# Schema2.net
KiCad netlist of a schematic drawn in Altium Designer
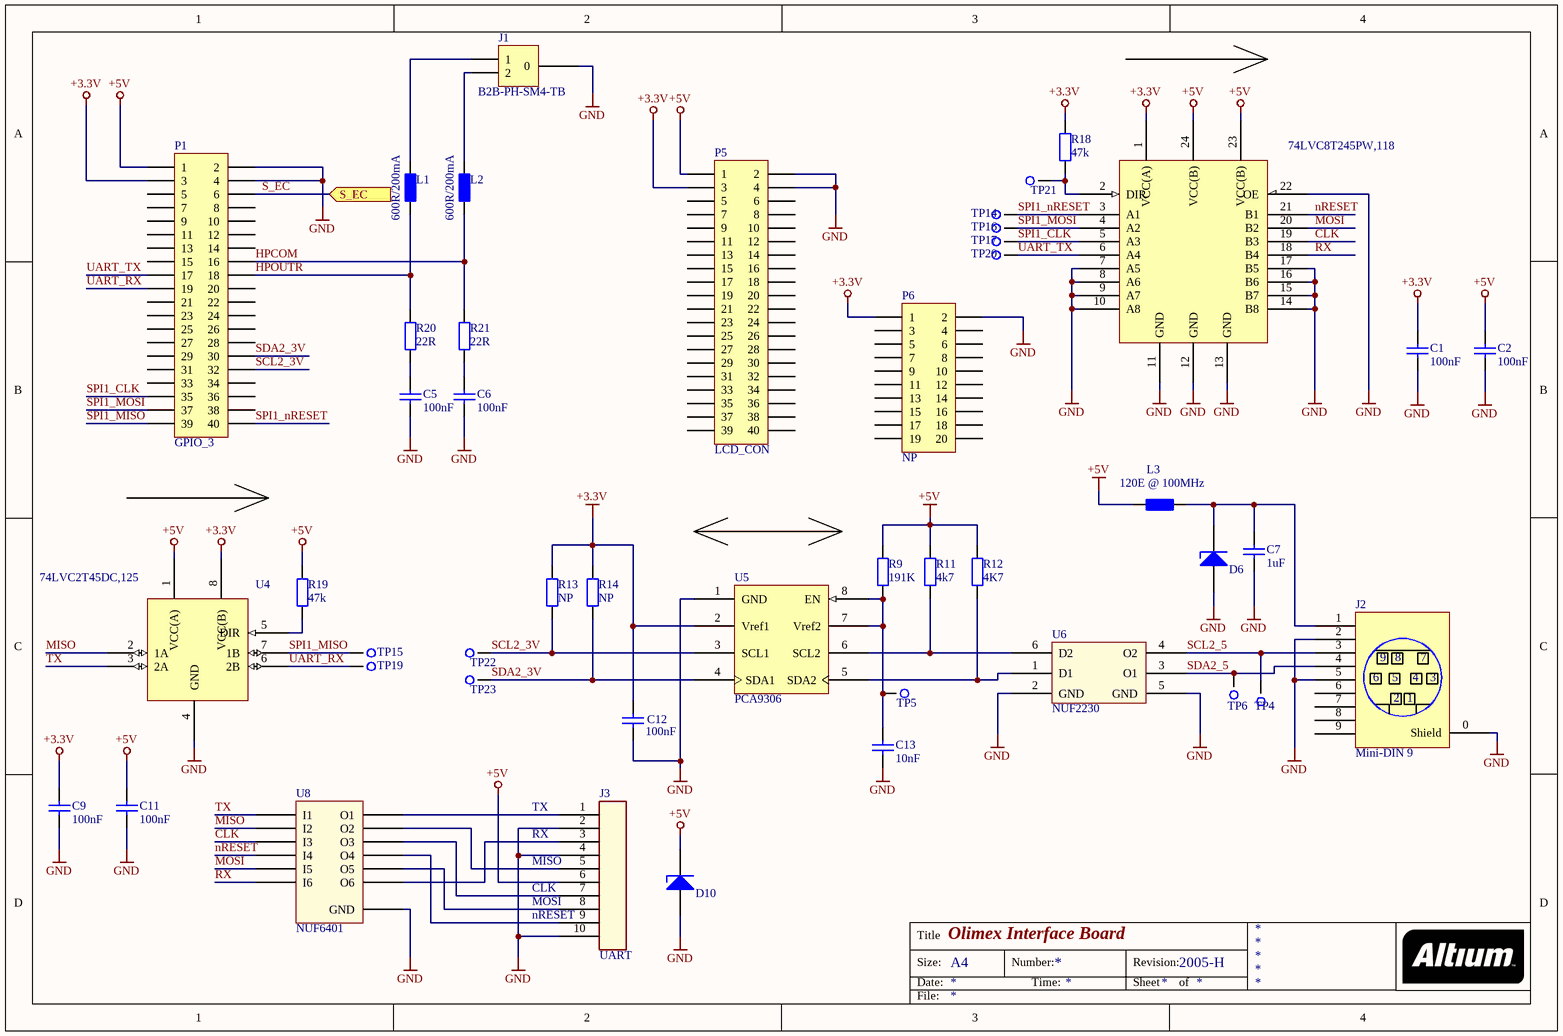
[diagram p0: Schema2.SchDoc]

(export (version "E")
  (design (tool "Eeschema 10.0.6"))
  (components
    (comp (ref "C1")
      (value "100nF")
      (footprint "C0805 (2012)")
      (description "Cap 100nF X7R 0805 10% 100V")
      (fields (field (name "MFG") "AVX"))
      (libsource (lib "Faber_SCH_lib") (part "Cap 100nF X7R 0805"))
    )
    (comp (ref "C2")
      (value "100nF")
      (footprint "C0805 (2012)")
      (description "Cap 100nF X7R 0805 10% 100V")
      (fields (field (name "MFG") "AVX"))
      (libsource (lib "Faber_SCH_lib") (part "Cap 100nF X7R 0805"))
    )
    (comp (ref "C5")
      (value "100nF")
      (footprint "C0805 (2012)")
      (description "Cap 100nF X7R 0805 10% 100V")
      (fields (field (name "MFG") "AVX"))
      (libsource (lib "Faber_SCH_lib") (part "Cap 100nF X7R 0805"))
    )
    (comp (ref "C6")
      (value "100nF")
      (footprint "C0805 (2012)")
      (description "Cap 100nF X7R 0805 10% 100V")
      (fields (field (name "MFG") "AVX"))
      (libsource (lib "Faber_SCH_lib") (part "Cap 100nF X7R 0805"))
    )
    (comp (ref "C7")
      (value "1uF")
      (footprint "CAPC1608X09N")
      (description "CAP CER 1UF 10V 10% X5R 0603")
      (fields
        (field (name "MANUFACTURER") "Murata Electronics North America")
        (field (name "MANUFACTURER PART NUMBER") "GRM188R61A105KA61D")
      )
      (libsource (lib "Marlin") (part "1uF/10V/0603"))
    )
    (comp (ref "C9")
      (value "100nF")
      (footprint "C0805 (2012)")
      (description "Cap 100nF X7R 0805 10% 100V")
      (fields (field (name "MFG") "AVX"))
      (libsource (lib "Faber_SCH_lib") (part "Cap 100nF X7R 0805"))
    )
    (comp (ref "C11")
      (value "100nF")
      (footprint "C0805 (2012)")
      (description "Cap 100nF X7R 0805 10% 100V")
      (fields (field (name "MFG") "AVX"))
      (libsource (lib "Faber_SCH_lib") (part "Cap 100nF X7R 0805"))
    )
    (comp (ref "C12")
      (value "100nF")
      (footprint "C0805 (2012)")
      (description "Cap 100nF X7R 0805 10% 100V")
      (fields (field (name "MFG") "AVX"))
      (libsource (lib "Faber_SCH_lib") (part "Cap 100nF X7R 0805"))
    )
    (comp (ref "C13")
      (value "10nF")
      (footprint "C0805 (2012)")
      (description "Cap 10nF X7R 0805 10% 100V")
      (fields (field (name "MFG") "AVX"))
      (libsource (lib "Faber_SCH_lib") (part "Cap 10nF X7R 0805"))
    )
    (comp (ref "D6")
      (value "ESD9X5.0ST5G")
      (footprint "SODFL100X40-2N")
      (description "TVS DIODE 5VWM 12.3VC SOD923")
      (fields (field (name "MFG") "ON Semiconductor"))
      (libsource (lib "Olimex interface board") (part "ESD9X5.0ST5G"))
    )
    (comp (ref "D10")
      (value "ESD9X5.0ST5G")
      (footprint "SODFL100X40-2N")
      (description "TVS DIODE 5VWM 12.3VC SOD923")
      (fields (field (name "MFG") "ON Semiconductor"))
      (libsource (lib "Olimex interface board") (part "ESD9X5.0ST5G"))
    )
    (comp (ref "J1")
      (value "B2B-PH-SM4-TB")
      (footprint "B2B-PH-SM4-TB")
      (description "JST B2B-PH-SM4-TB")
      (fields (field (name "MFG") "JST"))
      (libsource (lib "Olimex interface board") (part "Header 2_1"))
    )
    (comp (ref "J2")
      (value "Mini-DIN 9")
      (footprint "MD-90SM")
      (fields (field (name "MFG") "CUI Inc."))
      (libsource (lib "Olimex interface board") (part "Mini-DIN 9"))
    )
    (comp (ref "J3")
      (value "UART")
      (footprint "BOXHEADER-10P-straight")
      (description "RO CONN PR HDR BOX 10p")
      (fields (field (name "MFG") "Wurth"))
      (libsource (lib "Database_Faber") (part "HEADER 10"))
    )
    (comp (ref "L1")
      (value "600R/200mA")
      (footprint "R0805")
      (fields (field (name "MFG") "Fair-rite"))
      (libsource (lib "Ultimaker") (part "Ferriet Bead 600E"))
    )
    (comp (ref "L2")
      (value "600R/200mA")
      (footprint "R0805")
      (fields (field (name "MFG") "Fair-rite"))
      (libsource (lib "Ultimaker") (part "Ferriet Bead 600E"))
    )
    (comp (ref "L3")
      (value "120E @ 100MHz")
      (footprint "R0603")
      (description "FERRIET BLM18PG121SN1D 0603 MURATA")
      (fields (field (name "MFG") "Murata"))
      (libsource (lib "Ultimaker") (part "Ferriet Bead 120E"))
    )
    (comp (ref "P1")
      (value "GPIO_3")
      (footprint "M50-3152042")
      (description "HARWIN - M50-3152042 - SOCKET, DUAL ENTRY, SMT, 40WAY")
      (fields (field (name "MFG") "Harwin") (field (name "PUBLISHER") "Altium Limited"))
      (libsource (lib "Olimex interface board_1") (part "MHDR2X20"))
    )
    (comp (ref "P5")
      (value "LCD_CON")
      (footprint "M50-3152042")
      (description "HARWIN - M50-3152042 - SOCKET, DUAL ENTRY, SMT, 40WAY")
      (fields (field (name "MFG") "Harwin") (field (name "PUBLISHER") "Altium Limited"))
      (libsource (lib "Olimex interface board_1") (part "MHDR2X20"))
    )
    (comp (ref "P6")
      (value "NP")
      (footprint "HARWIN M20")
      (description "HARWIN M20")
      (fields (field (name "PUBLISHER") "Altium Limited"))
      (libsource (lib "Miscellaneous Connectors") (part "MHDR2X10"))
    )
    (comp (ref "R9")
      (value "191K")
      (footprint "R0805 (2012)")
      (description "Res 191K 0805 1% 125mW")
      (fields (field (name "MFG") "VISHAY DRALORIC"))
      (libsource (lib "Faber_SCH_lib") (part "Res 191K 0805"))
    )
    (comp (ref "R11")
      (value "4k7")
      (footprint "RESC1608X05N")
      (description "RES SMD 4.7K OHM 1% 1/10W 0603")
      (fields
        (field (name "MANUFACTURER") "Vishay Dale")
        (field (name "MANUFACTURER PART NUMBER") "CRCW06034K70FKEA")
      )
      (libsource (lib "altium-import") (part "root_1__Faber_SCH_lib.SchLib"))
    )
    (comp (ref "R12")
      (value "4K7")
      (footprint "RESC1608X05N")
      (description "RES SMD 4.7K OHM 1% 1/10W 0603")
      (fields
        (field (name "MANUFACTURER") "Vishay Dale")
        (field (name "MANUFACTURER PART NUMBER") "CRCW06034K70FKEA")
      )
      (libsource (lib "altium-import") (part "root_1__Faber_SCH_lib.SchLib"))
    )
    (comp (ref "R13")
      (value "NP")
      (footprint "R0805 (2012)")
      (description "Res 4.7K 0805 1% 100mW")
      (fields (field (name "MFG") "MULTICOMP"))
      (libsource (lib "Faber_SCH_lib") (part "Res 4.7K 0805"))
    )
    (comp (ref "R14")
      (value "NP")
      (footprint "R0805 (2012)")
      (description "Res 4.7K 0805 1% 100mW")
      (fields (field (name "MFG") "MULTICOMP"))
      (libsource (lib "Faber_SCH_lib") (part "Res 4.7K 0805"))
    )
    (comp (ref "R18")
      (value "47k")
      (footprint "RESC1608X05N")
      (description "RES 47.0K OHM 1/10W 1% 0603 SMD")
      (fields
        (field (name "MANUFACTURER") "Vishay Dale")
        (field (name "MANUFACTURER PART NUMBER") "CRCW060347K0FKEA")
      )
      (libsource (lib "Marlin") (part "47k/0603"))
    )
    (comp (ref "R19")
      (value "47k")
      (footprint "RESC1608X05N")
      (description "RES 47.0K OHM 1/10W 1% 0603 SMD")
      (fields
        (field (name "MANUFACTURER") "Vishay Dale")
        (field (name "MANUFACTURER PART NUMBER") "CRCW060347K0FKEA")
      )
      (libsource (lib "Marlin") (part "47k/0603"))
    )
    (comp (ref "R20")
      (value "22R")
      (footprint "RESC1608X05N")
      (description "RES 22R OHM 63mW 1% 0603 SMD")
      (fields (field (name "MFG") "MULTICOMP"))
      (libsource (lib "altium-import") (part "root_1_2.2k/0603_"))
    )
    (comp (ref "R21")
      (value "22R")
      (footprint "RESC1608X05N")
      (description "RES 22R OHM 63mW 1% 0603 SMD")
      (fields (field (name "MFG") "MULTICOMP"))
      (libsource (lib "altium-import") (part "root_1_2.2k/0603_"))
    )
    (comp (ref "TP4")
      (value "2mm")
      (footprint "TESTPOINT 2mm")
      (description "Testpoint, 2mm, round")
      (libsource (lib "Faber_SCH_lib") (part "Testpoint, 2mm, round"))
    )
    (comp (ref "TP5")
      (value "2mm")
      (footprint "TESTPOINT 2mm")
      (description "Testpoint, 2mm, round")
      (libsource (lib "Faber_SCH_lib") (part "Testpoint, 2mm, round"))
    )
    (comp (ref "TP6")
      (value "2mm")
      (footprint "TESTPOINT 2mm")
      (description "Testpoint, 2mm, round")
      (libsource (lib "Faber_SCH_lib") (part "Testpoint, 2mm, round"))
    )
    (comp (ref "TP14")
      (value "2mm")
      (footprint "TESTPOINT 2mm")
      (description "Testpoint, 2mm, round")
      (libsource (lib "Faber_SCH_lib") (part "Testpoint, 2mm, round"))
    )
    (comp (ref "TP15")
      (value "2mm")
      (footprint "TESTPOINT 2mm")
      (description "Testpoint, 2mm, round")
      (libsource (lib "Faber_SCH_lib") (part "Testpoint, 2mm, round"))
    )
    (comp (ref "TP16")
      (value "2mm")
      (footprint "TESTPOINT 2mm")
      (description "Testpoint, 2mm, round")
      (libsource (lib "Faber_SCH_lib") (part "Testpoint, 2mm, round"))
    )
    (comp (ref "TP17")
      (value "2mm")
      (footprint "TESTPOINT 2mm")
      (description "Testpoint, 2mm, round")
      (libsource (lib "Faber_SCH_lib") (part "Testpoint, 2mm, round"))
    )
    (comp (ref "TP19")
      (value "2mm")
      (footprint "TESTPOINT 2mm")
      (description "Testpoint, 2mm, round")
      (libsource (lib "Faber_SCH_lib") (part "Testpoint, 2mm, round"))
    )
    (comp (ref "TP20")
      (value "2mm")
      (footprint "TESTPOINT 2mm")
      (description "Testpoint, 2mm, round")
      (libsource (lib "Faber_SCH_lib") (part "Testpoint, 2mm, round"))
    )
    (comp (ref "TP21")
      (value "2mm")
      (footprint "TESTPOINT 2mm")
      (description "Testpoint, 2mm, round")
      (libsource (lib "Faber_SCH_lib") (part "Testpoint, 2mm, round"))
    )
    (comp (ref "TP22")
      (value "2mm")
      (footprint "TESTPOINT 2mm")
      (description "Testpoint, 2mm, round")
      (libsource (lib "Faber_SCH_lib") (part "Testpoint, 2mm, round"))
    )
    (comp (ref "TP23")
      (value "2mm")
      (footprint "TESTPOINT 2mm")
      (description "Testpoint, 2mm, round")
      (libsource (lib "Faber_SCH_lib") (part "Testpoint, 2mm, round"))
    )
    (comp (ref "U3")
      (value "74LVC8T245PW,118")
      (footprint "TSOP65P640X110-24N")
      (description "8-bit translaing transceiver")
      (fields (field (name "MFG") "NXP"))
      (libsource (lib "Olimex interface board") (part "74LVC8T245PW,118"))
    )
    (comp (ref "U4")
      (value "74LVC2T45DC,125")
      (footprint "TSSOP50P310X100-8N")
      (description "2-bit translaing transceiver")
      (fields (field (name "MFG") "NXP"))
      (libsource (lib "Olimex interface board") (part "74LVC2T45DC,125"))
    )
    (comp (ref "U5")
      (value "PCA9306")
      (footprint "IC SSOP-8")
      (description "IC PCA9306 Voltage Level translator")
      (fields (field (name "MFG") "TEXAS INSTRUMENTS"))
      (libsource (lib "Faber_SCH_lib") (part "IC PCA9306"))
    )
    (comp (ref "U6")
      (value "NUF2230")
      (footprint "SOTFL50P160X60-6N")
      (fields (field (name "MFG") "ON Semiconductor"))
      (libsource (lib "printehead") (part "NUF2230"))
    )
    (comp (ref "U8")
      (value "NUF6401")
      (footprint "SON50P140X100_HS-13N")
      (fields (field (name "MFG") "ON Semiconductor"))
      (libsource (lib "UltiController") (part "NUF6401"))
    )
  )
  (nets
    (net (code "1") (name "+3.3V") (class "Default")
      (node (ref "C1") (pin "1") (pinfunction "1_1") (pintype "passive"))
      (node (ref "C12") (pin "2") (pinfunction "2_2") (pintype "passive"))
      (node (ref "C9") (pin "1") (pinfunction "1_1") (pintype "passive"))
      (node (ref "P1") (pin "3") (pinfunction "3_3") (pintype "passive"))
      (node (ref "P5") (pin "3") (pinfunction "3_3") (pintype "passive"))
      (node (ref "P6") (pin "1") (pinfunction "1_1") (pintype "passive"))
      (node (ref "R13") (pin "2") (pinfunction "2_2") (pintype "passive"))
      (node (ref "R14") (pin "2") (pinfunction "2_2") (pintype "passive"))
      (node (ref "R18") (pin "1") (pinfunction "1_1") (pintype "passive"))
      (node (ref "U3") (pin "1") (pinfunction "VCC(A)_1") (pintype "power_in"))
      (node (ref "U4") (pin "8") (pinfunction "VCC(B)_8") (pintype "power_in"))
      (node (ref "U5") (pin "2") (pinfunction "Vref1_2") (pintype "power_in"))
    )
    (net (code "2") (name "+5V") (class "Default")
      (node (ref "C11") (pin "1") (pinfunction "1_1") (pintype "passive"))
      (node (ref "C2") (pin "1") (pinfunction "1_1") (pintype "passive"))
      (node (ref "D10") (pin "1") (pinfunction "K_1") (pintype "passive"))
      (node (ref "J3") (pin "6") (pinfunction "6_6") (pintype "passive"))
      (node (ref "L3") (pin "1") (pinfunction "1_1") (pintype "passive"))
      (node (ref "P1") (pin "1") (pinfunction "1_1") (pintype "passive"))
      (node (ref "P5") (pin "1") (pinfunction "1_1") (pintype "passive"))
      (node (ref "R11") (pin "2") (pinfunction "2_2") (pintype "passive"))
      (node (ref "R12") (pin "2") (pinfunction "2_2") (pintype "passive"))
      (node (ref "R19") (pin "1") (pinfunction "1_1") (pintype "passive"))
      (node (ref "R9") (pin "2") (pinfunction "2_2") (pintype "passive"))
      (node (ref "U3") (pin "23") (pinfunction "VCC(B)_23") (pintype "power_in"))
      (node (ref "U3") (pin "24") (pinfunction "VCC(B)_24") (pintype "power_in"))
      (node (ref "U4") (pin "1") (pinfunction "VCC(A)_1") (pintype "power_in"))
    )
    (net (code "3") (name "/CLK") (class "Default")
      (node (ref "U3") (pin "19") (pinfunction "B3_19") (pintype "passive"))
      (node (ref "U8") (pin "3") (pinfunction "I3_3") (pintype "passive"))
    )
    (net (code "4") (name "/HPCOM") (class "Default")
      (node (ref "L2") (pin "1") (pinfunction "1_1") (pintype "passive"))
      (node (ref "P1") (pin "16") (pinfunction "16_16") (pintype "passive"))
      (node (ref "R21") (pin "2") (pinfunction "2_2") (pintype "passive"))
    )
    (net (code "5") (name "/HPOUTR") (class "Default")
      (node (ref "L1") (pin "1") (pinfunction "1_1") (pintype "passive"))
      (node (ref "P1") (pin "18") (pinfunction "18_18") (pintype "passive"))
      (node (ref "R20") (pin "2") (pinfunction "2_2") (pintype "passive"))
    )
    (net (code "6") (name "/MISO") (class "Default")
      (node (ref "U4") (pin "2") (pinfunction "1A_2") (pintype "bidirectional"))
      (node (ref "U8") (pin "2") (pinfunction "I2_2") (pintype "passive"))
    )
    (net (code "7") (name "/MOSI") (class "Default")
      (node (ref "U3") (pin "20") (pinfunction "B2_20") (pintype "passive"))
      (node (ref "U8") (pin "5") (pinfunction "I5_5") (pintype "passive"))
    )
    (net (code "8") (name "/RX") (class "Default")
      (node (ref "U3") (pin "18") (pinfunction "B4_18") (pintype "passive"))
      (node (ref "U8") (pin "6") (pinfunction "I6_6") (pintype "passive"))
    )
    (net (code "9") (name "/SCL2_3V") (class "Default")
      (node (ref "P1") (pin "32") (pinfunction "32_32") (pintype "passive"))
      (node (ref "R13") (pin "1") (pinfunction "1_1") (pintype "passive"))
      (node (ref "TP22") (pin "1") (pinfunction "1_1") (pintype "passive"))
      (node (ref "U5") (pin "3") (pinfunction "SCL1_3") (pintype "passive"))
    )
    (net (code "10") (name "/SCL2_5") (class "Default")
      (node (ref "J2") (pin "3") (pinfunction "3_3") (pintype "passive"))
      (node (ref "TP4") (pin "1") (pinfunction "1_1") (pintype "passive"))
      (node (ref "U6") (pin "4") (pinfunction "O2_4") (pintype "passive"))
    )
    (net (code "11") (name "/SDA2_3V") (class "Default")
      (node (ref "P1") (pin "30") (pinfunction "30_30") (pintype "passive"))
      (node (ref "R14") (pin "1") (pinfunction "1_1") (pintype "passive"))
      (node (ref "TP23") (pin "1") (pinfunction "1_1") (pintype "passive"))
      (node (ref "U5") (pin "4") (pinfunction "SDA1_4") (pintype "passive"))
    )
    (net (code "12") (name "/SDA2_5") (class "Default")
      (node (ref "J2") (pin "4") (pinfunction "4_4") (pintype "passive"))
      (node (ref "TP6") (pin "1") (pinfunction "1_1") (pintype "passive"))
      (node (ref "U6") (pin "3") (pinfunction "O1_3") (pintype "passive"))
    )
    (net (code "13") (name "/SPI1_CLK") (class "Default")
      (node (ref "P1") (pin "35") (pinfunction "35_35") (pintype "passive"))
      (node (ref "TP17") (pin "1") (pinfunction "1_1") (pintype "passive"))
      (node (ref "U3") (pin "5") (pinfunction "A3_5") (pintype "passive"))
    )
    (net (code "14") (name "/SPI1_MISO") (class "Default")
      (node (ref "P1") (pin "39") (pinfunction "39_39") (pintype "passive"))
      (node (ref "TP15") (pin "1") (pinfunction "1_1") (pintype "passive"))
      (node (ref "U4") (pin "7") (pinfunction "1B_7") (pintype "bidirectional"))
    )
    (net (code "15") (name "/SPI1_MOSI") (class "Default")
      (node (ref "P1") (pin "37") (pinfunction "37_37") (pintype "passive"))
      (node (ref "TP16") (pin "1") (pinfunction "1_1") (pintype "passive"))
      (node (ref "U3") (pin "4") (pinfunction "A2_4") (pintype "passive"))
    )
    (net (code "16") (name "/SPI1_nRESET") (class "Default")
      (node (ref "P1") (pin "40") (pinfunction "40_40") (pintype "passive"))
      (node (ref "TP14") (pin "1") (pinfunction "1_1") (pintype "passive"))
      (node (ref "U3") (pin "3") (pinfunction "A1_3") (pintype "passive"))
    )
    (net (code "17") (name "/S_EC") (class "Default")
      (node (ref "P1") (pin "6") (pinfunction "6_6") (pintype "passive"))
    )
    (net (code "18") (name "/TX") (class "Default")
      (node (ref "U4") (pin "3") (pinfunction "2A_3") (pintype "bidirectional"))
      (node (ref "U8") (pin "1") (pinfunction "I1_1") (pintype "passive"))
    )
    (net (code "19") (name "/UART_RX") (class "Default")
      (node (ref "P1") (pin "19") (pinfunction "19_19") (pintype "passive"))
      (node (ref "TP19") (pin "1") (pinfunction "1_1") (pintype "passive"))
      (node (ref "U4") (pin "6") (pinfunction "2B_6") (pintype "bidirectional"))
    )
    (net (code "20") (name "/UART_TX") (class "Default")
      (node (ref "P1") (pin "17") (pinfunction "17_17") (pintype "passive"))
      (node (ref "TP20") (pin "1") (pinfunction "1_1") (pintype "passive"))
      (node (ref "U3") (pin "6") (pinfunction "A4_6") (pintype "passive"))
    )
    (net (code "21") (name "/nRESET") (class "Default")
      (node (ref "U3") (pin "21") (pinfunction "B1_21") (pintype "passive"))
      (node (ref "U8") (pin "4") (pinfunction "I4_4") (pintype "passive"))
    )
    (net (code "22") (name "GND") (class "Default")
      (node (ref "C1") (pin "2") (pinfunction "2_2") (pintype "passive"))
      (node (ref "C11") (pin "2") (pinfunction "2_2") (pintype "passive"))
      (node (ref "C12") (pin "1") (pinfunction "1_1") (pintype "passive"))
      (node (ref "C13") (pin "1") (pinfunction "1_1") (pintype "passive"))
      (node (ref "C2") (pin "2") (pinfunction "2_2") (pintype "passive"))
      (node (ref "C5") (pin "2") (pinfunction "2_2") (pintype "passive"))
      (node (ref "C6") (pin "2") (pinfunction "2_2") (pintype "passive"))
      (node (ref "C7") (pin "1") (pinfunction "1_1") (pintype "passive"))
      (node (ref "C9") (pin "2") (pinfunction "2_2") (pintype "passive"))
      (node (ref "D10") (pin "2") (pinfunction "A_2") (pintype "passive"))
      (node (ref "D6") (pin "2") (pinfunction "A_2") (pintype "passive"))
      (node (ref "J1") (pin "0") (pinfunction "0_0") (pintype "passive"))
      (node (ref "J2") (pin "0") (pinfunction "Shield_0") (pintype "passive"))
      (node (ref "J2") (pin "2") (pinfunction "2_2") (pintype "passive"))
      (node (ref "J2") (pin "5") (pinfunction "5_5") (pintype "passive"))
      (node (ref "J3") (pin "10") (pinfunction "10_10") (pintype "passive"))
      (node (ref "J3") (pin "2") (pinfunction "2_2") (pintype "passive"))
      (node (ref "J3") (pin "4") (pinfunction "4_4") (pintype "passive"))
      (node (ref "P1") (pin "2") (pinfunction "2_2") (pintype "passive"))
      (node (ref "P1") (pin "4") (pinfunction "4_4") (pintype "passive"))
      (node (ref "P5") (pin "2") (pinfunction "2_2") (pintype "passive"))
      (node (ref "P5") (pin "4") (pinfunction "4_4") (pintype "passive"))
      (node (ref "P6") (pin "2") (pinfunction "2_2") (pintype "passive"))
      (node (ref "U3") (pin "10") (pinfunction "A8_10") (pintype "passive"))
      (node (ref "U3") (pin "11") (pinfunction "GND_11") (pintype "power_in"))
      (node (ref "U3") (pin "12") (pinfunction "GND_12") (pintype "power_in"))
      (node (ref "U3") (pin "13") (pinfunction "GND_13") (pintype "power_in"))
      (node (ref "U3") (pin "14") (pinfunction "B8_14") (pintype "passive"))
      (node (ref "U3") (pin "15") (pinfunction "B7_15") (pintype "passive"))
      (node (ref "U3") (pin "16") (pinfunction "B6_16") (pintype "passive"))
      (node (ref "U3") (pin "17") (pinfunction "B5_17") (pintype "passive"))
      (node (ref "U3") (pin "22") (pinfunction "OE_22") (pintype "passive"))
      (node (ref "U3") (pin "7") (pinfunction "A5_7") (pintype "passive"))
      (node (ref "U3") (pin "8") (pinfunction "A6_8") (pintype "passive"))
      (node (ref "U3") (pin "9") (pinfunction "A7_9") (pintype "passive"))
      (node (ref "U4") (pin "4") (pinfunction "GND_4") (pintype "power_in"))
      (node (ref "U5") (pin "1") (pinfunction "GND_1") (pintype "power_in"))
      (node (ref "U6") (pin "2") (pinfunction "GND_2") (pintype "passive"))
      (node (ref "U6") (pin "5") (pinfunction "GND_5") (pintype "passive"))
      (node (ref "U8") (pin "13") (pinfunction "GND_13") (pintype "passive"))
    )
    (net (code "23") (name "Net-(C5-Pad1)") (class "Default")
      (node (ref "C5") (pin "1") (pinfunction "1_1") (pintype "passive"))
      (node (ref "R20") (pin "1") (pinfunction "1_1") (pintype "passive"))
    )
    (net (code "24") (name "Net-(C6-Pad1)") (class "Default")
      (node (ref "C6") (pin "1") (pinfunction "1_1") (pintype "passive"))
      (node (ref "R21") (pin "1") (pinfunction "1_1") (pintype "passive"))
    )
    (net (code "25") (name "Net-(D6-K)") (class "Default")
      (node (ref "C7") (pin "2") (pinfunction "2_2") (pintype "passive"))
      (node (ref "D6") (pin "1") (pinfunction "K_1") (pintype "passive"))
      (node (ref "J2") (pin "1") (pinfunction "1_1") (pintype "passive"))
      (node (ref "L3") (pin "2") (pinfunction "2_2") (pintype "passive"))
    )
    (net (code "26") (name "Net-(J1-Pad1)") (class "Default")
      (node (ref "J1") (pin "1") (pinfunction "1_1") (pintype "passive"))
      (node (ref "L1") (pin "2") (pinfunction "2_2") (pintype "passive"))
    )
    (net (code "27") (name "Net-(J1-Pad2)") (class "Default")
      (node (ref "J1") (pin "2") (pinfunction "2_2") (pintype "passive"))
      (node (ref "L2") (pin "2") (pinfunction "2_2") (pintype "passive"))
    )
    (net (code "28") (name "Net-(U3-DIR)") (class "Default")
      (node (ref "R18") (pin "2") (pinfunction "2_2") (pintype "passive"))
      (node (ref "TP21") (pin "1") (pinfunction "1_1") (pintype "passive"))
      (node (ref "U3") (pin "2") (pinfunction "DIR_2") (pintype "input"))
    )
    (net (code "29") (name "Net-(U4-DIR)") (class "Default")
      (node (ref "R19") (pin "2") (pinfunction "2_2") (pintype "passive"))
      (node (ref "U4") (pin "5") (pinfunction "DIR_5") (pintype "input"))
    )
    (net (code "30") (name "Net-(U5-EN)") (class "Default")
      (node (ref "C13") (pin "2") (pinfunction "2_2") (pintype "passive"))
      (node (ref "R9") (pin "1") (pinfunction "1_1") (pintype "passive"))
      (node (ref "TP5") (pin "1") (pinfunction "1_1") (pintype "passive"))
      (node (ref "U5") (pin "7") (pinfunction "Vref2_7") (pintype "power_in"))
      (node (ref "U5") (pin "8") (pinfunction "EN_8") (pintype "input"))
    )
    (net (code "31") (name "Net-(U5-SCL2)") (class "Default")
      (node (ref "R11") (pin "1") (pinfunction "1_1") (pintype "passive"))
      (node (ref "U5") (pin "6") (pinfunction "SCL2_6") (pintype "passive"))
      (node (ref "U6") (pin "6") (pinfunction "D2_6") (pintype "passive"))
    )
    (net (code "32") (name "Net-(U5-SDA2)") (class "Default")
      (node (ref "R12") (pin "1") (pinfunction "1_1") (pintype "passive"))
      (node (ref "U5") (pin "5") (pinfunction "SDA2_5") (pintype "passive"))
      (node (ref "U6") (pin "1") (pinfunction "D1_1") (pintype "passive"))
    )
    (net (code "33") (name "Net-(U8-O1)") (class "Default")
      (node (ref "J3") (pin "1") (pinfunction "1_1") (pintype "passive"))
      (node (ref "U8") (pin "12") (pinfunction "O1_12") (pintype "passive"))
    )
    (net (code "34") (name "Net-(U8-O2)") (class "Default")
      (node (ref "J3") (pin "5") (pinfunction "5_5") (pintype "passive"))
      (node (ref "U8") (pin "11") (pinfunction "O2_11") (pintype "passive"))
    )
    (net (code "35") (name "Net-(U8-O3)") (class "Default")
      (node (ref "J3") (pin "7") (pinfunction "7_7") (pintype "passive"))
      (node (ref "U8") (pin "10") (pinfunction "O3_10") (pintype "passive"))
    )
    (net (code "36") (name "Net-(U8-O4)") (class "Default")
      (node (ref "J3") (pin "9") (pinfunction "9_9") (pintype "passive"))
      (node (ref "U8") (pin "9") (pinfunction "O4_9") (pintype "passive"))
    )
    (net (code "37") (name "Net-(U8-O5)") (class "Default")
      (node (ref "J3") (pin "8") (pinfunction "8_8") (pintype "passive"))
      (node (ref "U8") (pin "8") (pinfunction "O5_8") (pintype "passive"))
    )
    (net (code "38") (name "Net-(U8-O6)") (class "Default")
      (node (ref "J3") (pin "3") (pinfunction "3_3") (pintype "passive"))
      (node (ref "U8") (pin "7") (pinfunction "O6_7") (pintype "passive"))
    )
    (net (code "39") (name "unconnected-(J2-Pad6)") (class "Default")
      (node (ref "J2") (pin "6") (pinfunction "6_6") (pintype "passive"))
    )
    (net (code "40") (name "unconnected-(J2-Pad7)") (class "Default")
      (node (ref "J2") (pin "7") (pinfunction "7_7") (pintype "passive"))
    )
    (net (code "41") (name "unconnected-(J2-Pad8)") (class "Default")
      (node (ref "J2") (pin "8") (pinfunction "8_8") (pintype "passive"))
    )
    (net (code "42") (name "unconnected-(J2-Pad9)") (class "Default")
      (node (ref "J2") (pin "9") (pinfunction "9_9") (pintype "passive"))
    )
    (net (code "43") (name "unconnected-(P1-Pad5)") (class "Default")
      (node (ref "P1") (pin "5") (pinfunction "5_5") (pintype "passive"))
    )
    (net (code "44") (name "unconnected-(P1-Pad7)") (class "Default")
      (node (ref "P1") (pin "7") (pinfunction "7_7") (pintype "passive"))
    )
    (net (code "45") (name "unconnected-(P1-Pad8)") (class "Default")
      (node (ref "P1") (pin "8") (pinfunction "8_8") (pintype "passive"))
    )
    (net (code "46") (name "unconnected-(P1-Pad9)") (class "Default")
      (node (ref "P1") (pin "9") (pinfunction "9_9") (pintype "passive"))
    )
    (net (code "47") (name "unconnected-(P1-Pad10)") (class "Default")
      (node (ref "P1") (pin "10") (pinfunction "10_10") (pintype "passive"))
    )
    (net (code "48") (name "unconnected-(P1-Pad11)") (class "Default")
      (node (ref "P1") (pin "11") (pinfunction "11_11") (pintype "passive"))
    )
    (net (code "49") (name "unconnected-(P1-Pad12)") (class "Default")
      (node (ref "P1") (pin "12") (pinfunction "12_12") (pintype "passive"))
    )
    (net (code "50") (name "unconnected-(P1-Pad13)") (class "Default")
      (node (ref "P1") (pin "13") (pinfunction "13_13") (pintype "passive"))
    )
    (net (code "51") (name "unconnected-(P1-Pad14)") (class "Default")
      (node (ref "P1") (pin "14") (pinfunction "14_14") (pintype "passive"))
    )
    (net (code "52") (name "unconnected-(P1-Pad15)") (class "Default")
      (node (ref "P1") (pin "15") (pinfunction "15_15") (pintype "passive"))
    )
    (net (code "53") (name "unconnected-(P1-Pad20)") (class "Default")
      (node (ref "P1") (pin "20") (pinfunction "20_20") (pintype "passive"))
    )
    (net (code "54") (name "unconnected-(P1-Pad21)") (class "Default")
      (node (ref "P1") (pin "21") (pinfunction "21_21") (pintype "passive"))
    )
    (net (code "55") (name "unconnected-(P1-Pad22)") (class "Default")
      (node (ref "P1") (pin "22") (pinfunction "22_22") (pintype "passive"))
    )
    (net (code "56") (name "unconnected-(P1-Pad23)") (class "Default")
      (node (ref "P1") (pin "23") (pinfunction "23_23") (pintype "passive"))
    )
    (net (code "57") (name "unconnected-(P1-Pad24)") (class "Default")
      (node (ref "P1") (pin "24") (pinfunction "24_24") (pintype "passive"))
    )
    (net (code "58") (name "unconnected-(P1-Pad25)") (class "Default")
      (node (ref "P1") (pin "25") (pinfunction "25_25") (pintype "passive"))
    )
    (net (code "59") (name "unconnected-(P1-Pad26)") (class "Default")
      (node (ref "P1") (pin "26") (pinfunction "26_26") (pintype "passive"))
    )
    (net (code "60") (name "unconnected-(P1-Pad27)") (class "Default")
      (node (ref "P1") (pin "27") (pinfunction "27_27") (pintype "passive"))
    )
    (net (code "61") (name "unconnected-(P1-Pad28)") (class "Default")
      (node (ref "P1") (pin "28") (pinfunction "28_28") (pintype "passive"))
    )
    (net (code "62") (name "unconnected-(P1-Pad29)") (class "Default")
      (node (ref "P1") (pin "29") (pinfunction "29_29") (pintype "passive"))
    )
    (net (code "63") (name "unconnected-(P1-Pad31)") (class "Default")
      (node (ref "P1") (pin "31") (pinfunction "31_31") (pintype "passive"))
    )
    (net (code "64") (name "unconnected-(P1-Pad33)") (class "Default")
      (node (ref "P1") (pin "33") (pinfunction "33_33") (pintype "passive"))
    )
    (net (code "65") (name "unconnected-(P1-Pad34)") (class "Default")
      (node (ref "P1") (pin "34") (pinfunction "34_34") (pintype "passive"))
    )
    (net (code "66") (name "unconnected-(P1-Pad36)") (class "Default")
      (node (ref "P1") (pin "36") (pinfunction "36_36") (pintype "passive"))
    )
    (net (code "67") (name "unconnected-(P1-Pad38)") (class "Default")
      (node (ref "P1") (pin "38") (pinfunction "38_38") (pintype "passive"))
    )
    (net (code "68") (name "unconnected-(P5-Pad5)") (class "Default")
      (node (ref "P5") (pin "5") (pinfunction "5_5") (pintype "passive"))
    )
    (net (code "69") (name "unconnected-(P5-Pad6)") (class "Default")
      (node (ref "P5") (pin "6") (pinfunction "6_6") (pintype "passive"))
    )
    (net (code "70") (name "unconnected-(P5-Pad7)") (class "Default")
      (node (ref "P5") (pin "7") (pinfunction "7_7") (pintype "passive"))
    )
    (net (code "71") (name "unconnected-(P5-Pad8)") (class "Default")
      (node (ref "P5") (pin "8") (pinfunction "8_8") (pintype "passive"))
    )
    (net (code "72") (name "unconnected-(P5-Pad9)") (class "Default")
      (node (ref "P5") (pin "9") (pinfunction "9_9") (pintype "passive"))
    )
    (net (code "73") (name "unconnected-(P5-Pad10)") (class "Default")
      (node (ref "P5") (pin "10") (pinfunction "10_10") (pintype "passive"))
    )
    (net (code "74") (name "unconnected-(P5-Pad11)") (class "Default")
      (node (ref "P5") (pin "11") (pinfunction "11_11") (pintype "passive"))
    )
    (net (code "75") (name "unconnected-(P5-Pad12)") (class "Default")
      (node (ref "P5") (pin "12") (pinfunction "12_12") (pintype "passive"))
    )
    (net (code "76") (name "unconnected-(P5-Pad13)") (class "Default")
      (node (ref "P5") (pin "13") (pinfunction "13_13") (pintype "passive"))
    )
    (net (code "77") (name "unconnected-(P5-Pad14)") (class "Default")
      (node (ref "P5") (pin "14") (pinfunction "14_14") (pintype "passive"))
    )
    (net (code "78") (name "unconnected-(P5-Pad15)") (class "Default")
      (node (ref "P5") (pin "15") (pinfunction "15_15") (pintype "passive"))
    )
    (net (code "79") (name "unconnected-(P5-Pad16)") (class "Default")
      (node (ref "P5") (pin "16") (pinfunction "16_16") (pintype "passive"))
    )
    (net (code "80") (name "unconnected-(P5-Pad17)") (class "Default")
      (node (ref "P5") (pin "17") (pinfunction "17_17") (pintype "passive"))
    )
    (net (code "81") (name "unconnected-(P5-Pad18)") (class "Default")
      (node (ref "P5") (pin "18") (pinfunction "18_18") (pintype "passive"))
    )
    (net (code "82") (name "unconnected-(P5-Pad19)") (class "Default")
      (node (ref "P5") (pin "19") (pinfunction "19_19") (pintype "passive"))
    )
    (net (code "83") (name "unconnected-(P5-Pad20)") (class "Default")
      (node (ref "P5") (pin "20") (pinfunction "20_20") (pintype "passive"))
    )
    (net (code "84") (name "unconnected-(P5-Pad21)") (class "Default")
      (node (ref "P5") (pin "21") (pinfunction "21_21") (pintype "passive"))
    )
    (net (code "85") (name "unconnected-(P5-Pad22)") (class "Default")
      (node (ref "P5") (pin "22") (pinfunction "22_22") (pintype "passive"))
    )
    (net (code "86") (name "unconnected-(P5-Pad23)") (class "Default")
      (node (ref "P5") (pin "23") (pinfunction "23_23") (pintype "passive"))
    )
    (net (code "87") (name "unconnected-(P5-Pad24)") (class "Default")
      (node (ref "P5") (pin "24") (pinfunction "24_24") (pintype "passive"))
    )
    (net (code "88") (name "unconnected-(P5-Pad25)") (class "Default")
      (node (ref "P5") (pin "25") (pinfunction "25_25") (pintype "passive"))
    )
    (net (code "89") (name "unconnected-(P5-Pad26)") (class "Default")
      (node (ref "P5") (pin "26") (pinfunction "26_26") (pintype "passive"))
    )
    (net (code "90") (name "unconnected-(P5-Pad27)") (class "Default")
      (node (ref "P5") (pin "27") (pinfunction "27_27") (pintype "passive"))
    )
    (net (code "91") (name "unconnected-(P5-Pad28)") (class "Default")
      (node (ref "P5") (pin "28") (pinfunction "28_28") (pintype "passive"))
    )
    (net (code "92") (name "unconnected-(P5-Pad29)") (class "Default")
      (node (ref "P5") (pin "29") (pinfunction "29_29") (pintype "passive"))
    )
    (net (code "93") (name "unconnected-(P5-Pad30)") (class "Default")
      (node (ref "P5") (pin "30") (pinfunction "30_30") (pintype "passive"))
    )
    (net (code "94") (name "unconnected-(P5-Pad31)") (class "Default")
      (node (ref "P5") (pin "31") (pinfunction "31_31") (pintype "passive"))
    )
    (net (code "95") (name "unconnected-(P5-Pad32)") (class "Default")
      (node (ref "P5") (pin "32") (pinfunction "32_32") (pintype "passive"))
    )
    (net (code "96") (name "unconnected-(P5-Pad33)") (class "Default")
      (node (ref "P5") (pin "33") (pinfunction "33_33") (pintype "passive"))
    )
    (net (code "97") (name "unconnected-(P5-Pad34)") (class "Default")
      (node (ref "P5") (pin "34") (pinfunction "34_34") (pintype "passive"))
    )
    (net (code "98") (name "unconnected-(P5-Pad35)") (class "Default")
      (node (ref "P5") (pin "35") (pinfunction "35_35") (pintype "passive"))
    )
    (net (code "99") (name "unconnected-(P5-Pad36)") (class "Default")
      (node (ref "P5") (pin "36") (pinfunction "36_36") (pintype "passive"))
    )
    (net (code "100") (name "unconnected-(P5-Pad37)") (class "Default")
      (node (ref "P5") (pin "37") (pinfunction "37_37") (pintype "passive"))
    )
    (net (code "101") (name "unconnected-(P5-Pad38)") (class "Default")
      (node (ref "P5") (pin "38") (pinfunction "38_38") (pintype "passive"))
    )
    (net (code "102") (name "unconnected-(P5-Pad39)") (class "Default")
      (node (ref "P5") (pin "39") (pinfunction "39_39") (pintype "passive"))
    )
    (net (code "103") (name "unconnected-(P5-Pad40)") (class "Default")
      (node (ref "P5") (pin "40") (pinfunction "40_40") (pintype "passive"))
    )
    (net (code "104") (name "unconnected-(P6-Pad3)") (class "Default")
      (node (ref "P6") (pin "3") (pinfunction "3_3") (pintype "passive"))
    )
    (net (code "105") (name "unconnected-(P6-Pad4)") (class "Default")
      (node (ref "P6") (pin "4") (pinfunction "4_4") (pintype "passive"))
    )
    (net (code "106") (name "unconnected-(P6-Pad5)") (class "Default")
      (node (ref "P6") (pin "5") (pinfunction "5_5") (pintype "passive"))
    )
    (net (code "107") (name "unconnected-(P6-Pad6)") (class "Default")
      (node (ref "P6") (pin "6") (pinfunction "6_6") (pintype "passive"))
    )
    (net (code "108") (name "unconnected-(P6-Pad7)") (class "Default")
      (node (ref "P6") (pin "7") (pinfunction "7_7") (pintype "passive"))
    )
    (net (code "109") (name "unconnected-(P6-Pad8)") (class "Default")
      (node (ref "P6") (pin "8") (pinfunction "8_8") (pintype "passive"))
    )
    (net (code "110") (name "unconnected-(P6-Pad9)") (class "Default")
      (node (ref "P6") (pin "9") (pinfunction "9_9") (pintype "passive"))
    )
    (net (code "111") (name "unconnected-(P6-Pad10)") (class "Default")
      (node (ref "P6") (pin "10") (pinfunction "10_10") (pintype "passive"))
    )
    (net (code "112") (name "unconnected-(P6-Pad11)") (class "Default")
      (node (ref "P6") (pin "11") (pinfunction "11_11") (pintype "passive"))
    )
    (net (code "113") (name "unconnected-(P6-Pad12)") (class "Default")
      (node (ref "P6") (pin "12") (pinfunction "12_12") (pintype "passive"))
    )
    (net (code "114") (name "unconnected-(P6-Pad13)") (class "Default")
      (node (ref "P6") (pin "13") (pinfunction "13_13") (pintype "passive"))
    )
    (net (code "115") (name "unconnected-(P6-Pad14)") (class "Default")
      (node (ref "P6") (pin "14") (pinfunction "14_14") (pintype "passive"))
    )
    (net (code "116") (name "unconnected-(P6-Pad15)") (class "Default")
      (node (ref "P6") (pin "15") (pinfunction "15_15") (pintype "passive"))
    )
    (net (code "117") (name "unconnected-(P6-Pad16)") (class "Default")
      (node (ref "P6") (pin "16") (pinfunction "16_16") (pintype "passive"))
    )
    (net (code "118") (name "unconnected-(P6-Pad17)") (class "Default")
      (node (ref "P6") (pin "17") (pinfunction "17_17") (pintype "passive"))
    )
    (net (code "119") (name "unconnected-(P6-Pad18)") (class "Default")
      (node (ref "P6") (pin "18") (pinfunction "18_18") (pintype "passive"))
    )
    (net (code "120") (name "unconnected-(P6-Pad19)") (class "Default")
      (node (ref "P6") (pin "19") (pinfunction "19_19") (pintype "passive"))
    )
    (net (code "121") (name "unconnected-(P6-Pad20)") (class "Default")
      (node (ref "P6") (pin "20") (pinfunction "20_20") (pintype "passive"))
    )
  )
)
